# fami.net
KiCad netlist of a schematic drawn in EAGLE
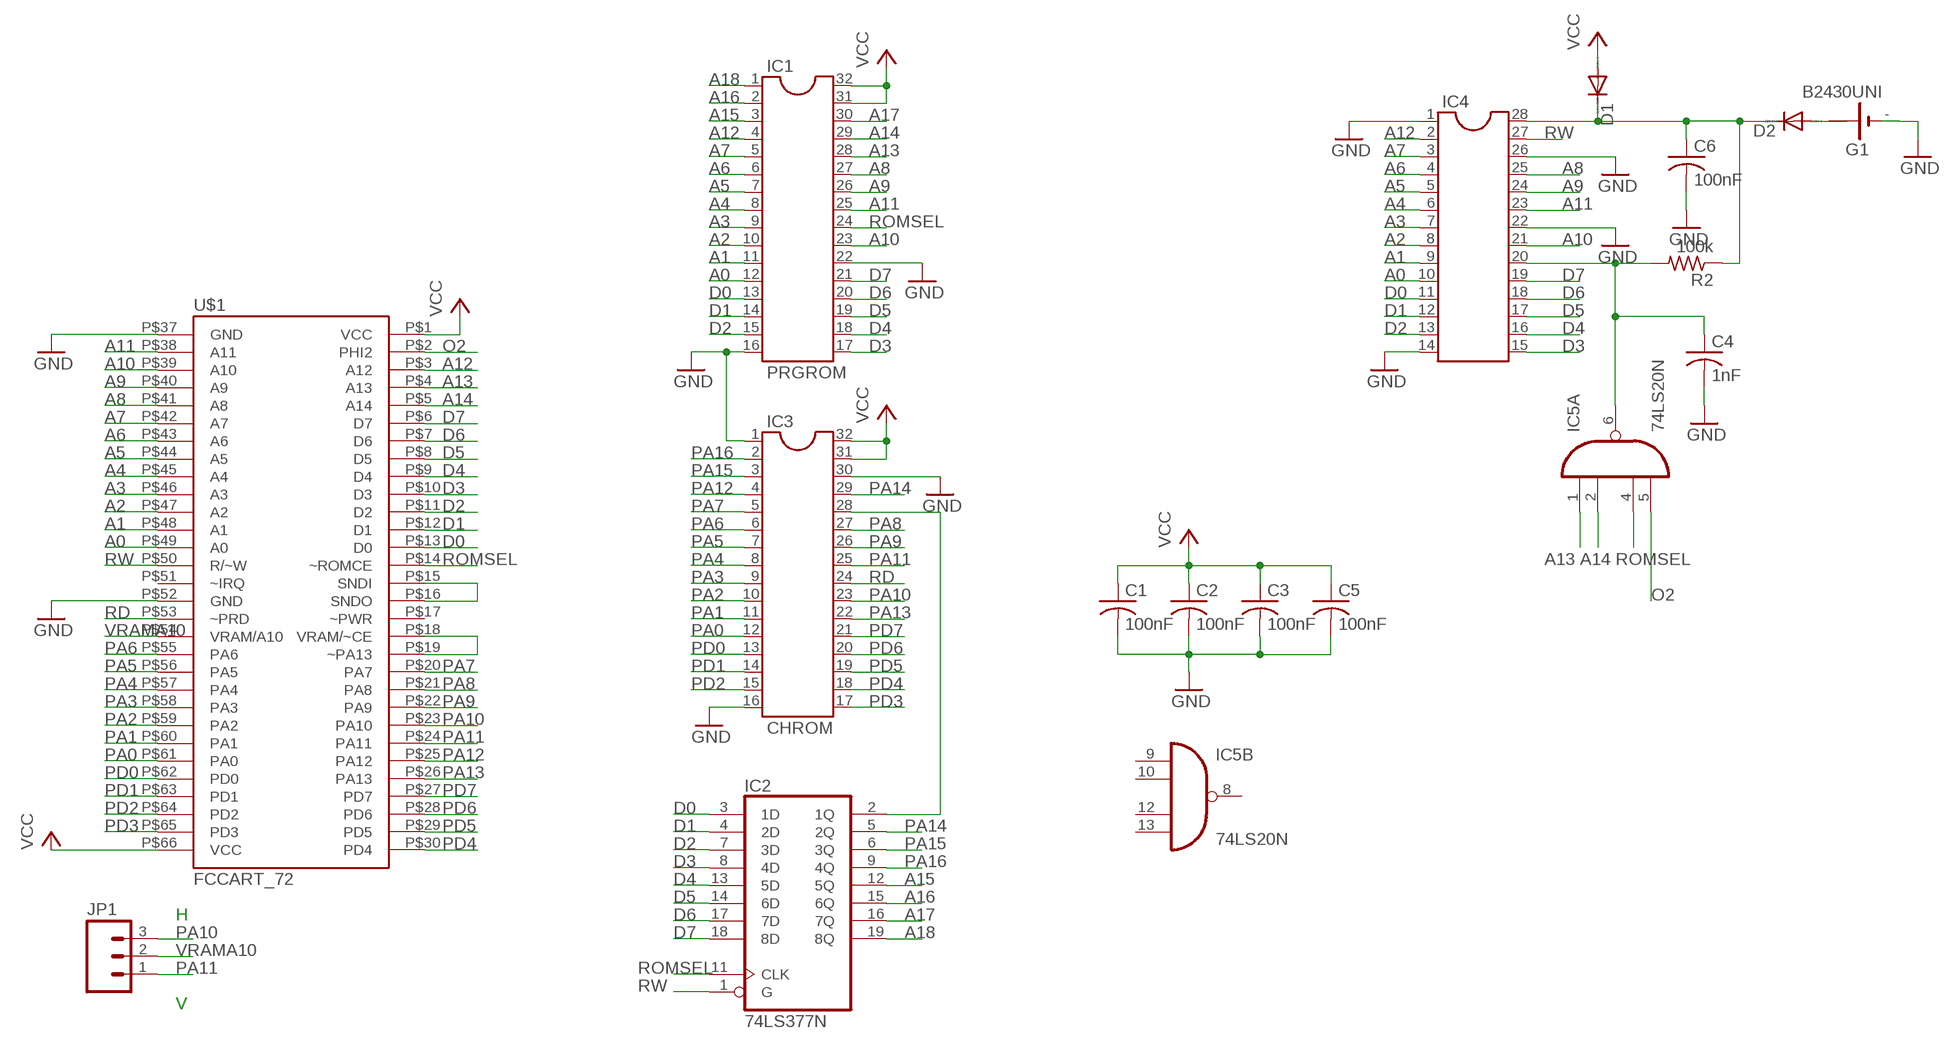
[diagram p0: schematic, sheet 1]

(export (version "E")
  (design (tool "Eeschema 10.0.6"))
  (components
    (comp (ref "C1")
      (value "100nF")
      (footprint "eagle-import:C025-025X050")
      (libsource (lib "eagle-import") (part "C-US025-025X050"))
    )
    (comp (ref "C2")
      (value "100nF")
      (footprint "eagle-import:C025-025X050")
      (libsource (lib "eagle-import") (part "C-US025-025X050"))
    )
    (comp (ref "C3")
      (value "100nF")
      (footprint "eagle-import:C025-025X050")
      (libsource (lib "eagle-import") (part "C-US025-025X050"))
    )
    (comp (ref "C4")
      (value "1nF")
      (footprint "eagle-import:C025-025X050")
      (libsource (lib "eagle-import") (part "C-US025-025X050"))
    )
    (comp (ref "C5")
      (value "100nF")
      (footprint "eagle-import:C025-025X050")
      (libsource (lib "eagle-import") (part "C-US025-025X050"))
    )
    (comp (ref "C6")
      (value "100nF")
      (footprint "eagle-import:C025-025X050")
      (libsource (lib "eagle-import") (part "C-US025-025X050"))
    )
    (comp (ref "D1")
      (value "DIODE-D-5")
      (footprint "eagle-import:D-5")
      (libsource (lib "eagle-import") (part "DIODE-D-5"))
    )
    (comp (ref "D2")
      (value "DIODE-D-5")
      (footprint "eagle-import:D-5")
      (libsource (lib "eagle-import") (part "DIODE-D-5"))
    )
    (comp (ref "G1")
      (value "B2430UNI")
      (footprint "eagle-import:B2430UNI")
      (libsource (lib "eagle-import") (part "B2430UNI"))
    )
    (comp (ref "IC1")
      (value "PRGROM")
      (footprint "eagle-import:DIL32")
      (libsource (lib "eagle-import") (part "DIL32"))
    )
    (comp (ref "IC2")
      (value "74LS377N")
      (footprint "eagle-import:DIL20")
      (libsource (lib "eagle-import") (part "74377NLS"))
    )
    (comp (ref "IC3")
      (value "CHROM")
      (footprint "eagle-import:DIL32")
      (libsource (lib "eagle-import") (part "DIL32"))
    )
    (comp (ref "IC4")
      (value "DIL28")
      (footprint "eagle-import:DIL28-6")
      (libsource (lib "eagle-import") (part "DIL28"))
    )
    (comp (ref "IC5")
      (value "74LS20N")
      (footprint "eagle-import:DIL14")
      (libsource (lib "eagle-import") (part "7420NLS"))
    )
    (comp (ref "JP1")
      (value "M03PTH")
      (footprint "eagle-import:1X03")
      (libsource (lib "eagle-import") (part "M03PTH"))
    )
    (comp (ref "R2")
      (value "100k")
      (footprint "eagle-import:0204_7")
      (libsource (lib "eagle-import") (part "R-US_0204/7"))
    )
    (comp (ref "U$1")
      (value "FCCART_72")
      (footprint "eagle-import:FCCART_72")
      (libsource (lib "eagle-import") (part "FCCART_72"))
    )
  )
  (nets
    (net (code "1") (name "/A0") (class "Default")
      (node (ref "IC1") (pin "12") (pinfunction "12_12") (pintype "passive"))
      (node (ref "IC4") (pin "10") (pinfunction "10_10") (pintype "passive"))
      (node (ref "U$1") (pin "P$49") (pinfunction "A0_P$49") (pintype "output"))
    )
    (net (code "2") (name "/A1") (class "Default")
      (node (ref "IC1") (pin "11") (pinfunction "11_11") (pintype "passive"))
      (node (ref "IC4") (pin "9") (pinfunction "9_9") (pintype "passive"))
      (node (ref "U$1") (pin "P$48") (pinfunction "A1_P$48") (pintype "output"))
    )
    (net (code "3") (name "/A2") (class "Default")
      (node (ref "IC1") (pin "10") (pinfunction "10_10") (pintype "passive"))
      (node (ref "IC4") (pin "8") (pinfunction "8_8") (pintype "passive"))
      (node (ref "U$1") (pin "P$47") (pinfunction "A2_P$47") (pintype "output"))
    )
    (net (code "4") (name "/A3") (class "Default")
      (node (ref "IC1") (pin "9") (pinfunction "9_9") (pintype "passive"))
      (node (ref "IC4") (pin "7") (pinfunction "7_7") (pintype "passive"))
      (node (ref "U$1") (pin "P$46") (pinfunction "A3_P$46") (pintype "output"))
    )
    (net (code "5") (name "/A4") (class "Default")
      (node (ref "IC1") (pin "8") (pinfunction "8_8") (pintype "passive"))
      (node (ref "IC4") (pin "6") (pinfunction "6_6") (pintype "passive"))
      (node (ref "U$1") (pin "P$45") (pinfunction "A4_P$45") (pintype "output"))
    )
    (net (code "6") (name "/A5") (class "Default")
      (node (ref "IC1") (pin "7") (pinfunction "7_7") (pintype "passive"))
      (node (ref "IC4") (pin "5") (pinfunction "5_5") (pintype "passive"))
      (node (ref "U$1") (pin "P$44") (pinfunction "A5_P$44") (pintype "output"))
    )
    (net (code "7") (name "/A6") (class "Default")
      (node (ref "IC1") (pin "6") (pinfunction "6_6") (pintype "passive"))
      (node (ref "IC4") (pin "4") (pinfunction "4_4") (pintype "passive"))
      (node (ref "U$1") (pin "P$43") (pinfunction "A6_P$43") (pintype "output"))
    )
    (net (code "8") (name "/A7") (class "Default")
      (node (ref "IC1") (pin "5") (pinfunction "5_5") (pintype "passive"))
      (node (ref "IC4") (pin "3") (pinfunction "3_3") (pintype "passive"))
      (node (ref "U$1") (pin "P$42") (pinfunction "A7_P$42") (pintype "output"))
    )
    (net (code "9") (name "/A8") (class "Default")
      (node (ref "IC1") (pin "27") (pinfunction "27_27") (pintype "passive"))
      (node (ref "IC4") (pin "25") (pinfunction "25_25") (pintype "passive"))
      (node (ref "U$1") (pin "P$41") (pinfunction "A8_P$41") (pintype "output"))
    )
    (net (code "10") (name "/A9") (class "Default")
      (node (ref "IC1") (pin "26") (pinfunction "26_26") (pintype "passive"))
      (node (ref "IC4") (pin "24") (pinfunction "24_24") (pintype "passive"))
      (node (ref "U$1") (pin "P$40") (pinfunction "A9_P$40") (pintype "output"))
    )
    (net (code "11") (name "/A10") (class "Default")
      (node (ref "IC1") (pin "23") (pinfunction "23_23") (pintype "passive"))
      (node (ref "IC4") (pin "21") (pinfunction "21_21") (pintype "passive"))
      (node (ref "U$1") (pin "P$39") (pinfunction "A10_P$39") (pintype "output"))
    )
    (net (code "12") (name "/A11") (class "Default")
      (node (ref "IC1") (pin "25") (pinfunction "25_25") (pintype "passive"))
      (node (ref "IC4") (pin "23") (pinfunction "23_23") (pintype "passive"))
      (node (ref "U$1") (pin "P$38") (pinfunction "A11_P$38") (pintype "output"))
    )
    (net (code "13") (name "/A12") (class "Default")
      (node (ref "IC1") (pin "4") (pinfunction "4_4") (pintype "passive"))
      (node (ref "IC4") (pin "2") (pinfunction "2_2") (pintype "passive"))
      (node (ref "U$1") (pin "P$3") (pinfunction "A12_P$3") (pintype "output"))
    )
    (net (code "14") (name "/A13") (class "Default")
      (node (ref "IC1") (pin "28") (pinfunction "28_28") (pintype "passive"))
      (node (ref "IC5") (pin "1") (pinfunction "I0_1") (pintype "input"))
      (node (ref "U$1") (pin "P$4") (pinfunction "A13_P$4") (pintype "output"))
    )
    (net (code "15") (name "/A14") (class "Default")
      (node (ref "IC1") (pin "29") (pinfunction "29_29") (pintype "passive"))
      (node (ref "IC5") (pin "2") (pinfunction "I1_2") (pintype "input"))
      (node (ref "U$1") (pin "P$5") (pinfunction "A14_P$5") (pintype "output"))
    )
    (net (code "16") (name "/A15") (class "Default")
      (node (ref "IC1") (pin "3") (pinfunction "3_3") (pintype "passive"))
      (node (ref "IC2") (pin "12") (pinfunction "5Q_12") (pintype "output"))
    )
    (net (code "17") (name "/A16") (class "Default")
      (node (ref "IC1") (pin "2") (pinfunction "2_2") (pintype "passive"))
      (node (ref "IC2") (pin "15") (pinfunction "6Q_15") (pintype "output"))
    )
    (net (code "18") (name "/A17") (class "Default")
      (node (ref "IC1") (pin "30") (pinfunction "30_30") (pintype "passive"))
      (node (ref "IC2") (pin "16") (pinfunction "7Q_16") (pintype "output"))
    )
    (net (code "19") (name "/A18") (class "Default")
      (node (ref "IC1") (pin "1") (pinfunction "1_1") (pintype "passive"))
      (node (ref "IC2") (pin "19") (pinfunction "8Q_19") (pintype "output"))
    )
    (net (code "20") (name "/D0") (class "Default")
      (node (ref "IC1") (pin "13") (pinfunction "13_13") (pintype "passive"))
      (node (ref "IC2") (pin "3") (pinfunction "1D_3") (pintype "input"))
      (node (ref "IC4") (pin "11") (pinfunction "11_11") (pintype "passive"))
      (node (ref "U$1") (pin "P$13") (pinfunction "D0_P$13") (pintype "output"))
    )
    (net (code "21") (name "/D1") (class "Default")
      (node (ref "IC1") (pin "14") (pinfunction "14_14") (pintype "passive"))
      (node (ref "IC2") (pin "4") (pinfunction "2D_4") (pintype "input"))
      (node (ref "IC4") (pin "12") (pinfunction "12_12") (pintype "passive"))
      (node (ref "U$1") (pin "P$12") (pinfunction "D1_P$12") (pintype "output"))
    )
    (net (code "22") (name "/D2") (class "Default")
      (node (ref "IC1") (pin "15") (pinfunction "15_15") (pintype "passive"))
      (node (ref "IC2") (pin "7") (pinfunction "3D_7") (pintype "input"))
      (node (ref "IC4") (pin "13") (pinfunction "13_13") (pintype "passive"))
      (node (ref "U$1") (pin "P$11") (pinfunction "D2_P$11") (pintype "output"))
    )
    (net (code "23") (name "/D3") (class "Default")
      (node (ref "IC1") (pin "17") (pinfunction "17_17") (pintype "passive"))
      (node (ref "IC2") (pin "8") (pinfunction "4D_8") (pintype "input"))
      (node (ref "IC4") (pin "15") (pinfunction "15_15") (pintype "passive"))
      (node (ref "U$1") (pin "P$10") (pinfunction "D3_P$10") (pintype "output"))
    )
    (net (code "24") (name "/D4") (class "Default")
      (node (ref "IC1") (pin "18") (pinfunction "18_18") (pintype "passive"))
      (node (ref "IC2") (pin "13") (pinfunction "5D_13") (pintype "input"))
      (node (ref "IC4") (pin "16") (pinfunction "16_16") (pintype "passive"))
      (node (ref "U$1") (pin "P$9") (pinfunction "D4_P$9") (pintype "output"))
    )
    (net (code "25") (name "/D5") (class "Default")
      (node (ref "IC1") (pin "19") (pinfunction "19_19") (pintype "passive"))
      (node (ref "IC2") (pin "14") (pinfunction "6D_14") (pintype "input"))
      (node (ref "IC4") (pin "17") (pinfunction "17_17") (pintype "passive"))
      (node (ref "U$1") (pin "P$8") (pinfunction "D5_P$8") (pintype "output"))
    )
    (net (code "26") (name "/D6") (class "Default")
      (node (ref "IC1") (pin "20") (pinfunction "20_20") (pintype "passive"))
      (node (ref "IC2") (pin "17") (pinfunction "7D_17") (pintype "input"))
      (node (ref "IC4") (pin "18") (pinfunction "18_18") (pintype "passive"))
      (node (ref "U$1") (pin "P$7") (pinfunction "D6_P$7") (pintype "output"))
    )
    (net (code "27") (name "/D7") (class "Default")
      (node (ref "IC1") (pin "21") (pinfunction "21_21") (pintype "passive"))
      (node (ref "IC2") (pin "18") (pinfunction "8D_18") (pintype "input"))
      (node (ref "IC4") (pin "19") (pinfunction "19_19") (pintype "passive"))
      (node (ref "U$1") (pin "P$6") (pinfunction "D7_P$6") (pintype "output"))
    )
    (net (code "28") (name "/O2") (class "Default")
      (node (ref "IC5") (pin "5") (pinfunction "I3_5") (pintype "input"))
      (node (ref "U$1") (pin "P$2") (pinfunction "PHI2_P$2") (pintype "output"))
    )
    (net (code "29") (name "/PA0") (class "Default")
      (node (ref "IC3") (pin "12") (pinfunction "12_12") (pintype "passive"))
      (node (ref "U$1") (pin "P$61") (pinfunction "PA0_P$61") (pintype "output"))
    )
    (net (code "30") (name "/PA1") (class "Default")
      (node (ref "IC3") (pin "11") (pinfunction "11_11") (pintype "passive"))
      (node (ref "U$1") (pin "P$60") (pinfunction "PA1_P$60") (pintype "output"))
    )
    (net (code "31") (name "/PA2") (class "Default")
      (node (ref "IC3") (pin "10") (pinfunction "10_10") (pintype "passive"))
      (node (ref "U$1") (pin "P$59") (pinfunction "PA2_P$59") (pintype "output"))
    )
    (net (code "32") (name "/PA3") (class "Default")
      (node (ref "IC3") (pin "9") (pinfunction "9_9") (pintype "passive"))
      (node (ref "U$1") (pin "P$58") (pinfunction "PA3_P$58") (pintype "output"))
    )
    (net (code "33") (name "/PA4") (class "Default")
      (node (ref "IC3") (pin "8") (pinfunction "8_8") (pintype "passive"))
      (node (ref "U$1") (pin "P$57") (pinfunction "PA4_P$57") (pintype "output"))
    )
    (net (code "34") (name "/PA5") (class "Default")
      (node (ref "IC3") (pin "7") (pinfunction "7_7") (pintype "passive"))
      (node (ref "U$1") (pin "P$56") (pinfunction "PA5_P$56") (pintype "output"))
    )
    (net (code "35") (name "/PA6") (class "Default")
      (node (ref "IC3") (pin "6") (pinfunction "6_6") (pintype "passive"))
      (node (ref "U$1") (pin "P$55") (pinfunction "PA6_P$55") (pintype "output"))
    )
    (net (code "36") (name "/PA7") (class "Default")
      (node (ref "IC3") (pin "5") (pinfunction "5_5") (pintype "passive"))
      (node (ref "U$1") (pin "P$20") (pinfunction "PA7_P$20") (pintype "output"))
    )
    (net (code "37") (name "/PA8") (class "Default")
      (node (ref "IC3") (pin "27") (pinfunction "27_27") (pintype "passive"))
      (node (ref "U$1") (pin "P$21") (pinfunction "PA8_P$21") (pintype "output"))
    )
    (net (code "38") (name "/PA9") (class "Default")
      (node (ref "IC3") (pin "26") (pinfunction "26_26") (pintype "passive"))
      (node (ref "U$1") (pin "P$22") (pinfunction "PA9_P$22") (pintype "output"))
    )
    (net (code "39") (name "/PA10") (class "Default")
      (node (ref "IC3") (pin "23") (pinfunction "23_23") (pintype "passive"))
      (node (ref "JP1") (pin "3") (pinfunction "3_3") (pintype "passive"))
      (node (ref "U$1") (pin "P$23") (pinfunction "PA10_P$23") (pintype "output"))
    )
    (net (code "40") (name "/PA11") (class "Default")
      (node (ref "IC3") (pin "25") (pinfunction "25_25") (pintype "passive"))
      (node (ref "JP1") (pin "1") (pinfunction "1_1") (pintype "passive"))
      (node (ref "U$1") (pin "P$24") (pinfunction "PA11_P$24") (pintype "output"))
    )
    (net (code "41") (name "/PA12") (class "Default")
      (node (ref "IC3") (pin "4") (pinfunction "4_4") (pintype "passive"))
      (node (ref "U$1") (pin "P$25") (pinfunction "PA12_P$25") (pintype "output"))
    )
    (net (code "42") (name "/PA13") (class "Default")
      (node (ref "IC3") (pin "22") (pinfunction "22_22") (pintype "passive"))
      (node (ref "U$1") (pin "P$26") (pinfunction "PA13_P$26") (pintype "output"))
    )
    (net (code "43") (name "/PA14") (class "Default")
      (node (ref "IC2") (pin "5") (pinfunction "2Q_5") (pintype "output"))
      (node (ref "IC3") (pin "29") (pinfunction "29_29") (pintype "passive"))
    )
    (net (code "44") (name "/PA15") (class "Default")
      (node (ref "IC2") (pin "6") (pinfunction "3Q_6") (pintype "output"))
      (node (ref "IC3") (pin "3") (pinfunction "3_3") (pintype "passive"))
    )
    (net (code "45") (name "/PA16") (class "Default")
      (node (ref "IC2") (pin "9") (pinfunction "4Q_9") (pintype "output"))
      (node (ref "IC3") (pin "2") (pinfunction "2_2") (pintype "passive"))
    )
    (net (code "46") (name "/PD0") (class "Default")
      (node (ref "IC3") (pin "13") (pinfunction "13_13") (pintype "passive"))
      (node (ref "U$1") (pin "P$62") (pinfunction "PD0_P$62") (pintype "bidirectional"))
    )
    (net (code "47") (name "/PD1") (class "Default")
      (node (ref "IC3") (pin "14") (pinfunction "14_14") (pintype "passive"))
      (node (ref "U$1") (pin "P$63") (pinfunction "PD1_P$63") (pintype "bidirectional"))
    )
    (net (code "48") (name "/PD2") (class "Default")
      (node (ref "IC3") (pin "15") (pinfunction "15_15") (pintype "passive"))
      (node (ref "U$1") (pin "P$64") (pinfunction "PD2_P$64") (pintype "bidirectional"))
    )
    (net (code "49") (name "/PD3") (class "Default")
      (node (ref "IC3") (pin "17") (pinfunction "17_17") (pintype "passive"))
      (node (ref "U$1") (pin "P$65") (pinfunction "PD3_P$65") (pintype "bidirectional"))
    )
    (net (code "50") (name "/PD4") (class "Default")
      (node (ref "IC3") (pin "18") (pinfunction "18_18") (pintype "passive"))
      (node (ref "U$1") (pin "P$30") (pinfunction "PD4_P$30") (pintype "bidirectional"))
    )
    (net (code "51") (name "/PD5") (class "Default")
      (node (ref "IC3") (pin "19") (pinfunction "19_19") (pintype "passive"))
      (node (ref "U$1") (pin "P$29") (pinfunction "PD5_P$29") (pintype "bidirectional"))
    )
    (net (code "52") (name "/PD6") (class "Default")
      (node (ref "IC3") (pin "20") (pinfunction "20_20") (pintype "passive"))
      (node (ref "U$1") (pin "P$28") (pinfunction "PD6_P$28") (pintype "bidirectional"))
    )
    (net (code "53") (name "/PD7") (class "Default")
      (node (ref "IC3") (pin "21") (pinfunction "21_21") (pintype "passive"))
      (node (ref "U$1") (pin "P$27") (pinfunction "PD7_P$27") (pintype "bidirectional"))
    )
    (net (code "54") (name "/RD") (class "Default")
      (node (ref "IC3") (pin "24") (pinfunction "24_24") (pintype "passive"))
      (node (ref "U$1") (pin "P$53") (pinfunction "~{PRD}_P$53") (pintype "output"))
    )
    (net (code "55") (name "/ROMSEL") (class "Default")
      (node (ref "IC1") (pin "24") (pinfunction "24_24") (pintype "passive"))
      (node (ref "IC2") (pin "11") (pinfunction "CLK_11") (pintype "input"))
      (node (ref "IC5") (pin "4") (pinfunction "I2_4") (pintype "input"))
      (node (ref "U$1") (pin "P$14") (pinfunction "~{ROMCE}_P$14") (pintype "output"))
    )
    (net (code "56") (name "/RW") (class "Default")
      (node (ref "IC2") (pin "1") (pinfunction "G_1") (pintype "input"))
      (node (ref "IC4") (pin "27") (pinfunction "27_27") (pintype "passive"))
      (node (ref "U$1") (pin "P$50") (pinfunction "R/~{W}_P$50") (pintype "output"))
    )
    (net (code "57") (name "/VRAMA10") (class "Default")
      (node (ref "JP1") (pin "2") (pinfunction "2_2") (pintype "passive"))
      (node (ref "U$1") (pin "P$54") (pinfunction "VRAM/A10_P$54") (pintype "input"))
    )
    (net (code "58") (name "GND") (class "Default")
      (node (ref "C1") (pin "2") (pinfunction "2_2") (pintype "passive"))
      (node (ref "C2") (pin "2") (pinfunction "2_2") (pintype "passive"))
      (node (ref "C3") (pin "2") (pinfunction "2_2") (pintype "passive"))
      (node (ref "C4") (pin "2") (pinfunction "2_2") (pintype "passive"))
      (node (ref "C5") (pin "2") (pinfunction "2_2") (pintype "passive"))
      (node (ref "C6") (pin "2") (pinfunction "2_2") (pintype "passive"))
      (node (ref "G1") (pin "-") (pinfunction "-_-") (pintype "passive"))
      (node (ref "G1") (pin "-@1") (pinfunction "-_-@1") (pintype "passive"))
      (node (ref "IC1") (pin "16") (pinfunction "16_16") (pintype "passive"))
      (node (ref "IC1") (pin "22") (pinfunction "22_22") (pintype "passive"))
      (node (ref "IC3") (pin "1") (pinfunction "1_1") (pintype "passive"))
      (node (ref "IC3") (pin "16") (pinfunction "16_16") (pintype "passive"))
      (node (ref "IC3") (pin "30") (pinfunction "30_30") (pintype "passive"))
      (node (ref "IC4") (pin "1") (pinfunction "1_1") (pintype "passive"))
      (node (ref "IC4") (pin "14") (pinfunction "14_14") (pintype "passive"))
      (node (ref "IC4") (pin "22") (pinfunction "22_22") (pintype "passive"))
      (node (ref "IC4") (pin "26") (pinfunction "26_26") (pintype "passive"))
      (node (ref "U$1") (pin "P$37") (pinfunction "GND_P$37") (pintype "power_in"))
      (node (ref "U$1") (pin "P$52") (pinfunction "GND_P$52") (pintype "power_in"))
    )
    (net (code "59") (name "Net-(C6-Pad1)") (class "Default")
      (node (ref "C6") (pin "1") (pinfunction "1_1") (pintype "passive"))
      (node (ref "D1") (pin "C") (pinfunction "C_C") (pintype "passive"))
      (node (ref "D2") (pin "C") (pinfunction "C_C") (pintype "passive"))
      (node (ref "IC4") (pin "28") (pinfunction "28_28") (pintype "passive"))
      (node (ref "R2") (pin "1") (pinfunction "1_1") (pintype "passive"))
    )
    (net (code "60") (name "Net-(G1-+)") (class "Default")
      (node (ref "D2") (pin "A") (pinfunction "A_A") (pintype "passive"))
      (node (ref "G1") (pin "+@4") (pinfunction "+_+@4") (pintype "passive"))
    )
    (net (code "61") (name "Net-(IC2A-1Q)") (class "Default")
      (node (ref "IC2") (pin "2") (pinfunction "1Q_2") (pintype "output"))
      (node (ref "IC3") (pin "28") (pinfunction "28_28") (pintype "passive"))
    )
    (net (code "62") (name "Net-(IC5A-O)") (class "Default")
      (node (ref "C4") (pin "1") (pinfunction "1_1") (pintype "passive"))
      (node (ref "IC4") (pin "20") (pinfunction "20_20") (pintype "passive"))
      (node (ref "IC5") (pin "6") (pinfunction "O_6") (pintype "output"))
      (node (ref "R2") (pin "2") (pinfunction "2_2") (pintype "passive"))
    )
    (net (code "63") (name "Net-(U$1-SNDI)") (class "Default")
      (node (ref "U$1") (pin "P$15") (pinfunction "SNDI_P$15") (pintype "output"))
      (node (ref "U$1") (pin "P$16") (pinfunction "SNDO_P$16") (pintype "input"))
    )
    (net (code "64") (name "Net-(U$1-VRAM{slash}~{CE})") (class "Default")
      (node (ref "U$1") (pin "P$18") (pinfunction "VRAM/~{CE}_P$18") (pintype "input"))
      (node (ref "U$1") (pin "P$19") (pinfunction "~{PA13}_P$19") (pintype "output"))
    )
    (net (code "65") (name "VCC") (class "Default")
      (node (ref "C1") (pin "1") (pinfunction "1_1") (pintype "passive"))
      (node (ref "C2") (pin "1") (pinfunction "1_1") (pintype "passive"))
      (node (ref "C3") (pin "1") (pinfunction "1_1") (pintype "passive"))
      (node (ref "C5") (pin "1") (pinfunction "1_1") (pintype "passive"))
      (node (ref "D1") (pin "A") (pinfunction "A_A") (pintype "passive"))
      (node (ref "IC1") (pin "31") (pinfunction "31_31") (pintype "passive"))
      (node (ref "IC1") (pin "32") (pinfunction "32_32") (pintype "passive"))
      (node (ref "IC3") (pin "31") (pinfunction "31_31") (pintype "passive"))
      (node (ref "IC3") (pin "32") (pinfunction "32_32") (pintype "passive"))
      (node (ref "U$1") (pin "P$1") (pinfunction "VCC_P$1") (pintype "power_in"))
      (node (ref "U$1") (pin "P$66") (pinfunction "VCC_P$66") (pintype "power_in"))
    )
    (net (code "66") (name "unconnected-(IC5B-I0-Pad9)") (class "Default")
      (node (ref "IC5") (pin "9") (pinfunction "I0_9") (pintype "input"))
    )
    (net (code "67") (name "unconnected-(IC5B-I1-Pad10)") (class "Default")
      (node (ref "IC5") (pin "10") (pinfunction "I1_10") (pintype "input"))
    )
    (net (code "68") (name "unconnected-(IC5B-I2-Pad12)") (class "Default")
      (node (ref "IC5") (pin "12") (pinfunction "I2_12") (pintype "input"))
    )
    (net (code "69") (name "unconnected-(IC5B-I3-Pad13)") (class "Default")
      (node (ref "IC5") (pin "13") (pinfunction "I3_13") (pintype "input"))
    )
    (net (code "70") (name "unconnected-(IC5B-O-Pad8)") (class "Default")
      (node (ref "IC5") (pin "8") (pinfunction "O_8") (pintype "output"))
    )
    (net (code "71") (name "unconnected-(U$1-~{IRQ}-PadP$51)") (class "Default")
      (node (ref "U$1") (pin "P$51") (pinfunction "~{IRQ}_P$51") (pintype "output"))
    )
    (net (code "72") (name "unconnected-(U$1-~{PWR}-PadP$17)") (class "Default")
      (node (ref "U$1") (pin "P$17") (pinfunction "~{PWR}_P$17") (pintype "output"))
    )
  )
)
